# main.net
KiCad netlist of a schematic drawn in Altium Designer
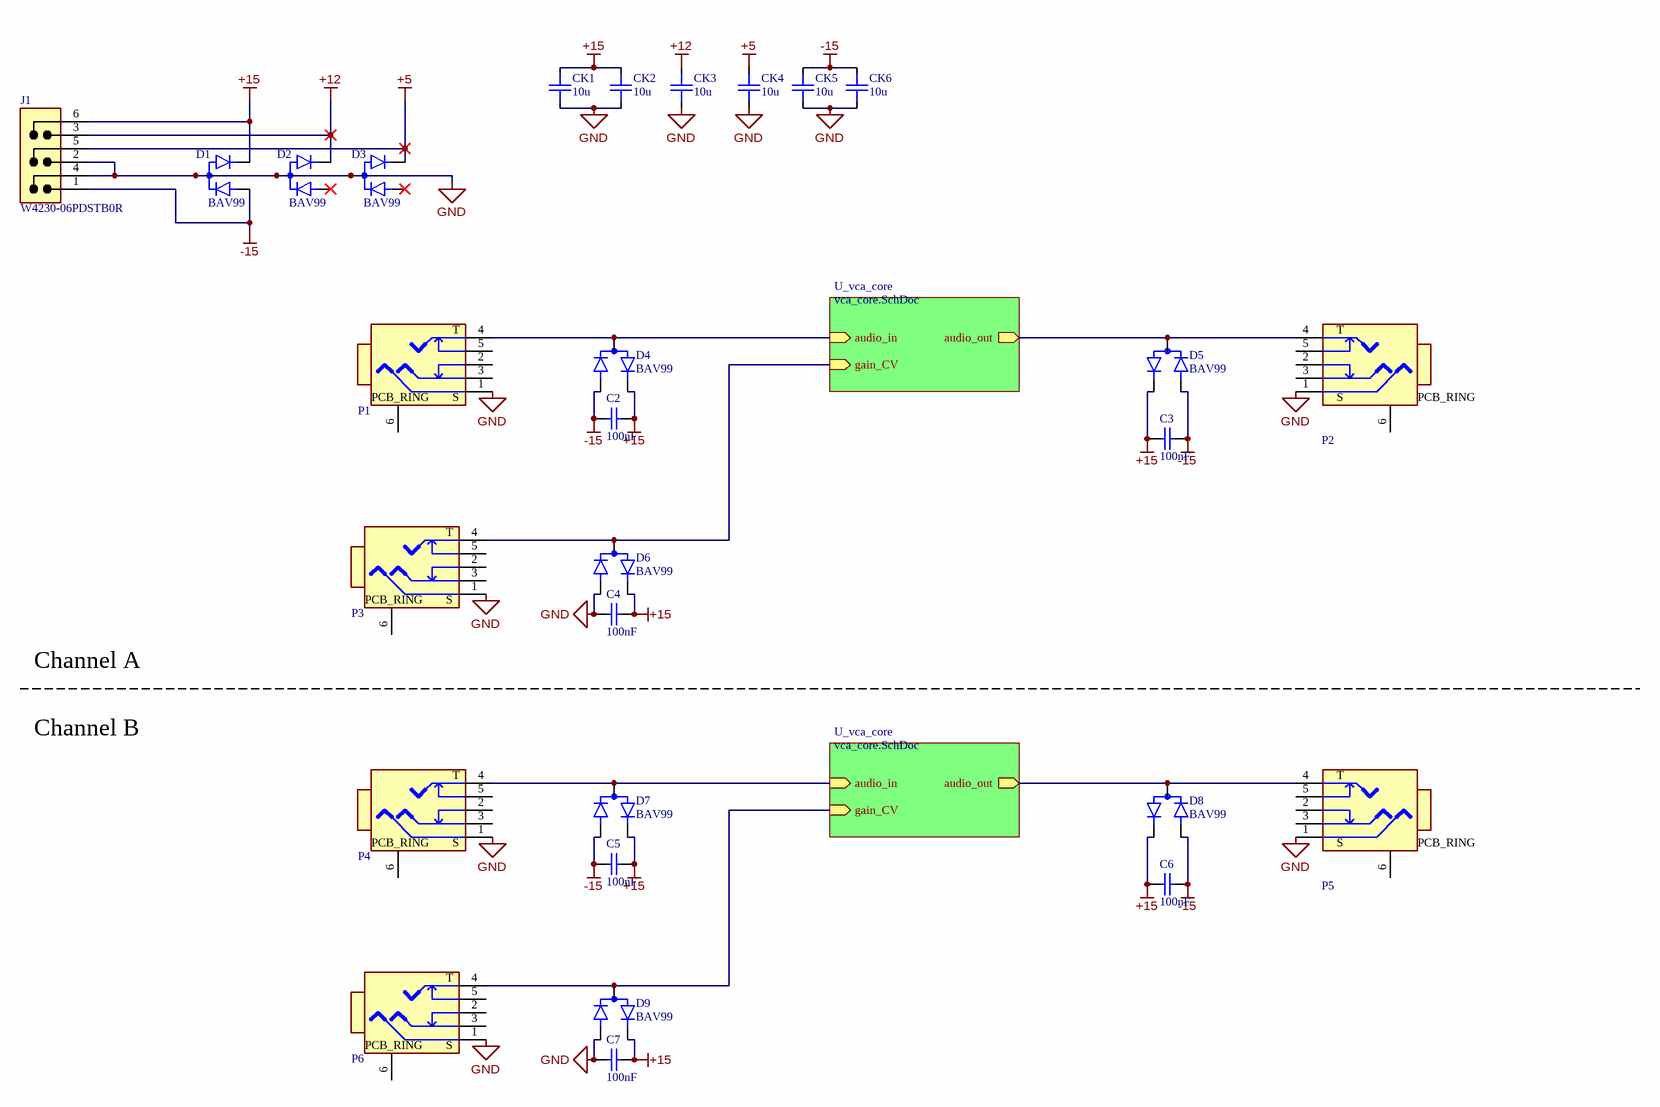
[diagram p0: main.SchDoc]

(export (version "E")
  (design (tool "Eeschema 10.0.6"))
  (components
    (comp (ref "C2")
      (value "100nF")
      (footprint "WCAP-CSGP_0603_L1.6W0.8H0.8_Reflow")
      (description "WCAP-CSGP Multilayer Ceramic Chip Capacitor, General Purpose, size 0603, X7R, 100nF, 50V")
      (fields
        (field (name "MANUFACTURER") "Wurth Elektronik")
        (field (name "MANUFACTURER PART NUMBER") "885012206095")
      )
      (libsource (lib "Altium_WCAP-CSGP (rev22a)") (part "885012206095"))
    )
    (comp (ref "C3")
      (value "100nF")
      (footprint "WCAP-CSGP_0603_L1.6W0.8H0.8_Reflow")
      (description "WCAP-CSGP Multilayer Ceramic Chip Capacitor, General Purpose, size 0603, X7R, 100nF, 50V")
      (fields
        (field (name "MANUFACTURER") "Wurth Elektronik")
        (field (name "MANUFACTURER PART NUMBER") "885012206095")
      )
      (libsource (lib "Altium_WCAP-CSGP (rev22a)") (part "885012206095"))
    )
    (comp (ref "C4")
      (value "100nF")
      (footprint "WCAP-CSGP_0603_L1.6W0.8H0.8_Reflow")
      (description "WCAP-CSGP Multilayer Ceramic Chip Capacitor, General Purpose, size 0603, X7R, 100nF, 50V")
      (fields
        (field (name "MANUFACTURER") "Wurth Elektronik")
        (field (name "MANUFACTURER PART NUMBER") "885012206095")
      )
      (libsource (lib "Altium_WCAP-CSGP (rev22a)") (part "885012206095"))
    )
    (comp (ref "C5")
      (value "100nF")
      (footprint "WCAP-CSGP_0603_L1.6W0.8H0.8_Reflow")
      (description "WCAP-CSGP Multilayer Ceramic Chip Capacitor, General Purpose, size 0603, X7R, 100nF, 50V")
      (fields
        (field (name "MANUFACTURER") "Wurth Elektronik")
        (field (name "MANUFACTURER PART NUMBER") "885012206095")
      )
      (libsource (lib "Altium_WCAP-CSGP (rev22a)") (part "885012206095"))
    )
    (comp (ref "C6")
      (value "100nF")
      (footprint "WCAP-CSGP_0603_L1.6W0.8H0.8_Reflow")
      (description "WCAP-CSGP Multilayer Ceramic Chip Capacitor, General Purpose, size 0603, X7R, 100nF, 50V")
      (fields
        (field (name "MANUFACTURER") "Wurth Elektronik")
        (field (name "MANUFACTURER PART NUMBER") "885012206095")
      )
      (libsource (lib "Altium_WCAP-CSGP (rev22a)") (part "885012206095"))
    )
    (comp (ref "C7")
      (value "100nF")
      (footprint "WCAP-CSGP_0603_L1.6W0.8H0.8_Reflow")
      (description "WCAP-CSGP Multilayer Ceramic Chip Capacitor, General Purpose, size 0603, X7R, 100nF, 50V")
      (fields
        (field (name "MANUFACTURER") "Wurth Elektronik")
        (field (name "MANUFACTURER PART NUMBER") "885012206095")
      )
      (libsource (lib "Altium_WCAP-CSGP (rev22a)") (part "885012206095"))
    )
    (comp (ref "CK1")
      (value "10u")
      (footprint "CAPC3225X27N(SMC1210)")
      (description "C; 10u; 50V; 10%; X7R; ??;")
      (fields
        (field (name "MANUFACTURER") "Murata: GRM32ER71H106KA12L;;Samsung Electro-mechanics: CL32B106KBJNNNE")
      )
      (libsource (lib "altium_sql") (part "CK"))
    )
    (comp (ref "CK2")
      (value "10u")
      (footprint "CAPC3225X27N(SMC1210)")
      (description "C; 10u; 50V; 10%; X7R; ??;")
      (fields
        (field (name "MANUFACTURER") "Murata: GRM32ER71H106KA12L;;Samsung Electro-mechanics: CL32B106KBJNNNE")
      )
      (libsource (lib "altium_sql") (part "CK"))
    )
    (comp (ref "CK3")
      (value "10u")
      (footprint "CAPC3225X27N(SMC1210)")
      (description "C; 10u; 50V; 10%; X7R; ??;")
      (fields
        (field (name "MANUFACTURER") "Murata: GRM32ER71H106KA12L;;Samsung Electro-mechanics: CL32B106KBJNNNE")
      )
      (libsource (lib "altium_sql") (part "CK"))
    )
    (comp (ref "CK4")
      (value "10u")
      (footprint "CAPC3225X27N(SMC1210)")
      (description "C; 10u; 50V; 10%; X7R; ??;")
      (fields
        (field (name "MANUFACTURER") "Murata: GRM32ER71H106KA12L;;Samsung Electro-mechanics: CL32B106KBJNNNE")
      )
      (libsource (lib "altium_sql") (part "CK"))
    )
    (comp (ref "CK5")
      (value "10u")
      (footprint "CAPC3225X27N(SMC1210)")
      (description "C; 10u; 50V; 10%; X7R; ??;")
      (fields
        (field (name "MANUFACTURER") "Murata: GRM32ER71H106KA12L;;Samsung Electro-mechanics: CL32B106KBJNNNE")
      )
      (libsource (lib "altium_sql") (part "CK"))
    )
    (comp (ref "CK6")
      (value "10u")
      (footprint "CAPC3225X27N(SMC1210)")
      (description "C; 10u; 50V; 10%; X7R; ??;")
      (fields
        (field (name "MANUFACTURER") "Murata: GRM32ER71H106KA12L;;Samsung Electro-mechanics: CL32B106KBJNNNE")
      )
      (libsource (lib "altium_sql") (part "CK"))
    )
    (comp (ref "D1")
      (value "BAV99")
      (footprint "SOT95P230X110-3N(SOT23)")
      (libsource (lib "Kubikova integrovana knihovna ") (part "BAV99"))
    )
    (comp (ref "D2")
      (value "BAV99")
      (footprint "SOT95P230X110-3N(SOT23)")
      (libsource (lib "Kubikova integrovana knihovna ") (part "BAV99"))
    )
    (comp (ref "D3")
      (value "BAV99")
      (footprint "SOT95P230X110-3N(SOT23)")
      (libsource (lib "Kubikova integrovana knihovna ") (part "BAV99"))
    )
    (comp (ref "D4")
      (value "BAV99")
      (footprint "SOT95P230X110-3N(SOT23)")
      (libsource (lib "Kubikova integrovana knihovna ") (part "BAV99"))
    )
    (comp (ref "D5")
      (value "BAV99")
      (footprint "SOT95P230X110-3N(SOT23)")
      (libsource (lib "Kubikova integrovana knihovna ") (part "BAV99"))
    )
    (comp (ref "D6")
      (value "BAV99")
      (footprint "SOT95P230X110-3N(SOT23)")
      (libsource (lib "Kubikova integrovana knihovna ") (part "BAV99"))
    )
    (comp (ref "D7")
      (value "BAV99")
      (footprint "SOT95P230X110-3N(SOT23)")
      (libsource (lib "Kubikova integrovana knihovna ") (part "BAV99"))
    )
    (comp (ref "D8")
      (value "BAV99")
      (footprint "SOT95P230X110-3N(SOT23)")
      (libsource (lib "Kubikova integrovana knihovna ") (part "BAV99"))
    )
    (comp (ref "D9")
      (value "BAV99")
      (footprint "SOT95P230X110-3N(SOT23)")
      (libsource (lib "Kubikova integrovana knihovna ") (part "BAV99"))
    )
    (comp (ref "J1")
      (value "W4230-06PDSTB0R")
      (footprint "W4230-06PDS")
      (description "Con; Micro Fit 3.0; 6x; PCB; Straight; 250V; 5A; Male; Tin; ??;")
      (fields
        (field (name "MANUFACTURER") "HSUAN MAO: W4230-06PDSTB0R;;HSUAN MAO: W4230-06PDSTB0N;;HSM: W4230-06PDSTB0R;;HSM: W4230-06PDSTB0N")
      )
      (libsource (lib "altium_sql") (part "EJ_2X3PIN_L_MALE"))
    )
    (comp (ref "P1")
      (value "NYS232")
      (footprint "NYS232")
      (description "6.3 mm jack, right angle, THT")
      (libsource (lib "Kubikova integrovana knihovna ") (part "NYS232"))
    )
    (comp (ref "P2")
      (value "NYS232")
      (footprint "NYS232")
      (description "6.3 mm jack, right angle, THT")
      (libsource (lib "") (part "NYS232_1"))
    )
    (comp (ref "P3")
      (value "NYS232")
      (footprint "NYS232")
      (description "6.3 mm jack, right angle, THT")
      (libsource (lib "Kubikova integrovana knihovna ") (part "NYS232"))
    )
    (comp (ref "P4")
      (value "NYS232")
      (footprint "NYS232")
      (description "6.3 mm jack, right angle, THT")
      (libsource (lib "Kubikova integrovana knihovna ") (part "NYS232"))
    )
    (comp (ref "P5")
      (value "NYS232")
      (footprint "NYS232")
      (description "6.3 mm jack, right angle, THT")
      (libsource (lib "") (part "NYS232_1"))
    )
    (comp (ref "P6")
      (value "NYS232")
      (footprint "NYS232")
      (description "6.3 mm jack, right angle, THT")
      (libsource (lib "Kubikova integrovana knihovna ") (part "NYS232"))
    )
  )
  (nets
    (net (code "1") (name "+5") (class "Default")
      (node (ref "CK4") (pin "1") (pinfunction "1_1") (pintype "passive"))
      (node (ref "D3") (pin "2") (pinfunction "C2_2") (pintype "passive"))
      (node (ref "J1") (pin "5") (pinfunction "5_5") (pintype "passive"))
    )
    (net (code "2") (name "+12") (class "Default")
      (node (ref "CK3") (pin "1") (pinfunction "1_1") (pintype "passive"))
      (node (ref "D2") (pin "2") (pinfunction "C2_2") (pintype "passive"))
      (node (ref "J1") (pin "3") (pinfunction "3_3") (pintype "passive"))
    )
    (net (code "3") (name "+15") (class "Default")
      (node (ref "C2") (pin "2") (pinfunction "2_2") (pintype "passive"))
      (node (ref "C3") (pin "2") (pinfunction "2_2") (pintype "passive"))
      (node (ref "C4") (pin "2") (pinfunction "2_2") (pintype "passive"))
      (node (ref "C5") (pin "2") (pinfunction "2_2") (pintype "passive"))
      (node (ref "C6") (pin "2") (pinfunction "2_2") (pintype "passive"))
      (node (ref "C7") (pin "2") (pinfunction "2_2") (pintype "passive"))
      (node (ref "CK1") (pin "1") (pinfunction "1_1") (pintype "passive"))
      (node (ref "CK2") (pin "1") (pinfunction "1_1") (pintype "passive"))
      (node (ref "D1") (pin "2") (pinfunction "C2_2") (pintype "passive"))
      (node (ref "D4") (pin "2") (pinfunction "C2_2") (pintype "passive"))
      (node (ref "D5") (pin "2") (pinfunction "C2_2") (pintype "passive"))
      (node (ref "D6") (pin "2") (pinfunction "C2_2") (pintype "passive"))
      (node (ref "D7") (pin "2") (pinfunction "C2_2") (pintype "passive"))
      (node (ref "D8") (pin "2") (pinfunction "C2_2") (pintype "passive"))
      (node (ref "D9") (pin "2") (pinfunction "C2_2") (pintype "passive"))
      (node (ref "J1") (pin "6") (pinfunction "6_6") (pintype "passive"))
    )
    (net (code "4") (name "-15") (class "Default")
      (node (ref "C2") (pin "1") (pinfunction "1_1") (pintype "passive"))
      (node (ref "C3") (pin "1") (pinfunction "1_1") (pintype "passive"))
      (node (ref "C5") (pin "1") (pinfunction "1_1") (pintype "passive"))
      (node (ref "C6") (pin "1") (pinfunction "1_1") (pintype "passive"))
      (node (ref "CK5") (pin "1") (pinfunction "1_1") (pintype "passive"))
      (node (ref "CK6") (pin "1") (pinfunction "1_1") (pintype "passive"))
      (node (ref "D1") (pin "1") (pinfunction "A1_1") (pintype "passive"))
      (node (ref "D4") (pin "1") (pinfunction "A1_1") (pintype "passive"))
      (node (ref "D5") (pin "1") (pinfunction "A1_1") (pintype "passive"))
      (node (ref "D7") (pin "1") (pinfunction "A1_1") (pintype "passive"))
      (node (ref "D8") (pin "1") (pinfunction "A1_1") (pintype "passive"))
      (node (ref "J1") (pin "1") (pinfunction "1_1") (pintype "passive"))
    )
    (net (code "5") (name "/audio_in") (class "Default")
      (node (ref "D7") (pin "3") (pinfunction "C1A2_3") (pintype "passive"))
      (node (ref "P4") (pin "4") (pinfunction "TN_4") (pintype "passive"))
    )
    (net (code "6") (name "/audio_in_1") (class "Default")
      (node (ref "D4") (pin "3") (pinfunction "C1A2_3") (pintype "passive"))
      (node (ref "P1") (pin "4") (pinfunction "TN_4") (pintype "passive"))
    )
    (net (code "7") (name "/audio_out") (class "Default")
      (node (ref "D5") (pin "3") (pinfunction "C1A2_3") (pintype "passive"))
      (node (ref "P2") (pin "4") (pinfunction "TN_4") (pintype "passive"))
    )
    (net (code "8") (name "/audio_out_1") (class "Default")
      (node (ref "D8") (pin "3") (pinfunction "C1A2_3") (pintype "passive"))
      (node (ref "P5") (pin "4") (pinfunction "TN_4") (pintype "passive"))
    )
    (net (code "9") (name "/gain_CV") (class "Default")
      (node (ref "D9") (pin "3") (pinfunction "C1A2_3") (pintype "passive"))
      (node (ref "P6") (pin "4") (pinfunction "TN_4") (pintype "passive"))
    )
    (net (code "10") (name "/gain_CV_1") (class "Default")
      (node (ref "D6") (pin "3") (pinfunction "C1A2_3") (pintype "passive"))
      (node (ref "P3") (pin "4") (pinfunction "TN_4") (pintype "passive"))
    )
    (net (code "11") (name "GND") (class "Default")
      (node (ref "C4") (pin "1") (pinfunction "1_1") (pintype "passive"))
      (node (ref "C7") (pin "1") (pinfunction "1_1") (pintype "passive"))
      (node (ref "CK1") (pin "2") (pinfunction "2_2") (pintype "passive"))
      (node (ref "CK2") (pin "2") (pinfunction "2_2") (pintype "passive"))
      (node (ref "CK3") (pin "2") (pinfunction "2_2") (pintype "passive"))
      (node (ref "CK4") (pin "2") (pinfunction "2_2") (pintype "passive"))
      (node (ref "CK5") (pin "2") (pinfunction "2_2") (pintype "passive"))
      (node (ref "CK6") (pin "2") (pinfunction "2_2") (pintype "passive"))
      (node (ref "D1") (pin "3") (pinfunction "C1A2_3") (pintype "passive"))
      (node (ref "D2") (pin "3") (pinfunction "C1A2_3") (pintype "passive"))
      (node (ref "D3") (pin "3") (pinfunction "C1A2_3") (pintype "passive"))
      (node (ref "D6") (pin "1") (pinfunction "A1_1") (pintype "passive"))
      (node (ref "D9") (pin "1") (pinfunction "A1_1") (pintype "passive"))
      (node (ref "J1") (pin "2") (pinfunction "2_2") (pintype "passive"))
      (node (ref "J1") (pin "4") (pinfunction "4_4") (pintype "passive"))
      (node (ref "P1") (pin "1") (pinfunction "S_1") (pintype "passive"))
      (node (ref "P2") (pin "1") (pinfunction "S_1") (pintype "passive"))
      (node (ref "P3") (pin "1") (pinfunction "S_1") (pintype "passive"))
      (node (ref "P4") (pin "1") (pinfunction "S_1") (pintype "passive"))
      (node (ref "P5") (pin "1") (pinfunction "S_1") (pintype "passive"))
      (node (ref "P6") (pin "1") (pinfunction "S_1") (pintype "passive"))
    )
    (net (code "12") (name "unconnected-(D2-A1-Pad1)") (class "Default")
      (node (ref "D2") (pin "1") (pinfunction "A1_1") (pintype "passive+no_connect"))
    )
    (net (code "13") (name "unconnected-(D3-A1-Pad1)") (class "Default")
      (node (ref "D3") (pin "1") (pinfunction "A1_1") (pintype "passive+no_connect"))
    )
    (net (code "14") (name "unconnected-(P1-PCB_RING-Pad6)") (class "Default")
      (node (ref "P1") (pin "6") (pinfunction "PCB_RING_6") (pintype "passive"))
    )
    (net (code "15") (name "unconnected-(P1-R-Pad3)") (class "Default")
      (node (ref "P1") (pin "3") (pinfunction "R_3") (pintype "passive"))
    )
    (net (code "16") (name "unconnected-(P1-RN-Pad2)") (class "Default")
      (node (ref "P1") (pin "2") (pinfunction "RN_2") (pintype "passive"))
    )
    (net (code "17") (name "unconnected-(P1-T-Pad5)") (class "Default")
      (node (ref "P1") (pin "5") (pinfunction "T_5") (pintype "passive"))
    )
    (net (code "18") (name "unconnected-(P2-PCB_RING-Pad6)") (class "Default")
      (node (ref "P2") (pin "6") (pinfunction "PCB_RING_6") (pintype "passive"))
    )
    (net (code "19") (name "unconnected-(P2-R-Pad3)") (class "Default")
      (node (ref "P2") (pin "3") (pinfunction "R_3") (pintype "passive"))
    )
    (net (code "20") (name "unconnected-(P2-RN-Pad2)") (class "Default")
      (node (ref "P2") (pin "2") (pinfunction "RN_2") (pintype "passive"))
    )
    (net (code "21") (name "unconnected-(P2-T-Pad5)") (class "Default")
      (node (ref "P2") (pin "5") (pinfunction "T_5") (pintype "passive"))
    )
    (net (code "22") (name "unconnected-(P3-PCB_RING-Pad6)") (class "Default")
      (node (ref "P3") (pin "6") (pinfunction "PCB_RING_6") (pintype "passive"))
    )
    (net (code "23") (name "unconnected-(P3-R-Pad3)") (class "Default")
      (node (ref "P3") (pin "3") (pinfunction "R_3") (pintype "passive"))
    )
    (net (code "24") (name "unconnected-(P3-RN-Pad2)") (class "Default")
      (node (ref "P3") (pin "2") (pinfunction "RN_2") (pintype "passive"))
    )
    (net (code "25") (name "unconnected-(P3-T-Pad5)") (class "Default")
      (node (ref "P3") (pin "5") (pinfunction "T_5") (pintype "passive"))
    )
    (net (code "26") (name "unconnected-(P4-PCB_RING-Pad6)") (class "Default")
      (node (ref "P4") (pin "6") (pinfunction "PCB_RING_6") (pintype "passive"))
    )
    (net (code "27") (name "unconnected-(P4-R-Pad3)") (class "Default")
      (node (ref "P4") (pin "3") (pinfunction "R_3") (pintype "passive"))
    )
    (net (code "28") (name "unconnected-(P4-RN-Pad2)") (class "Default")
      (node (ref "P4") (pin "2") (pinfunction "RN_2") (pintype "passive"))
    )
    (net (code "29") (name "unconnected-(P4-T-Pad5)") (class "Default")
      (node (ref "P4") (pin "5") (pinfunction "T_5") (pintype "passive"))
    )
    (net (code "30") (name "unconnected-(P5-PCB_RING-Pad6)") (class "Default")
      (node (ref "P5") (pin "6") (pinfunction "PCB_RING_6") (pintype "passive"))
    )
    (net (code "31") (name "unconnected-(P5-R-Pad3)") (class "Default")
      (node (ref "P5") (pin "3") (pinfunction "R_3") (pintype "passive"))
    )
    (net (code "32") (name "unconnected-(P5-RN-Pad2)") (class "Default")
      (node (ref "P5") (pin "2") (pinfunction "RN_2") (pintype "passive"))
    )
    (net (code "33") (name "unconnected-(P5-T-Pad5)") (class "Default")
      (node (ref "P5") (pin "5") (pinfunction "T_5") (pintype "passive"))
    )
    (net (code "34") (name "unconnected-(P6-PCB_RING-Pad6)") (class "Default")
      (node (ref "P6") (pin "6") (pinfunction "PCB_RING_6") (pintype "passive"))
    )
    (net (code "35") (name "unconnected-(P6-R-Pad3)") (class "Default")
      (node (ref "P6") (pin "3") (pinfunction "R_3") (pintype "passive"))
    )
    (net (code "36") (name "unconnected-(P6-RN-Pad2)") (class "Default")
      (node (ref "P6") (pin "2") (pinfunction "RN_2") (pintype "passive"))
    )
    (net (code "37") (name "unconnected-(P6-T-Pad5)") (class "Default")
      (node (ref "P6") (pin "5") (pinfunction "T_5") (pintype "passive"))
    )
  )
)
